# Tracksoar-Thermistor-Buzzer-Shield.net
KiCad netlist of a schematic drawn in EAGLE
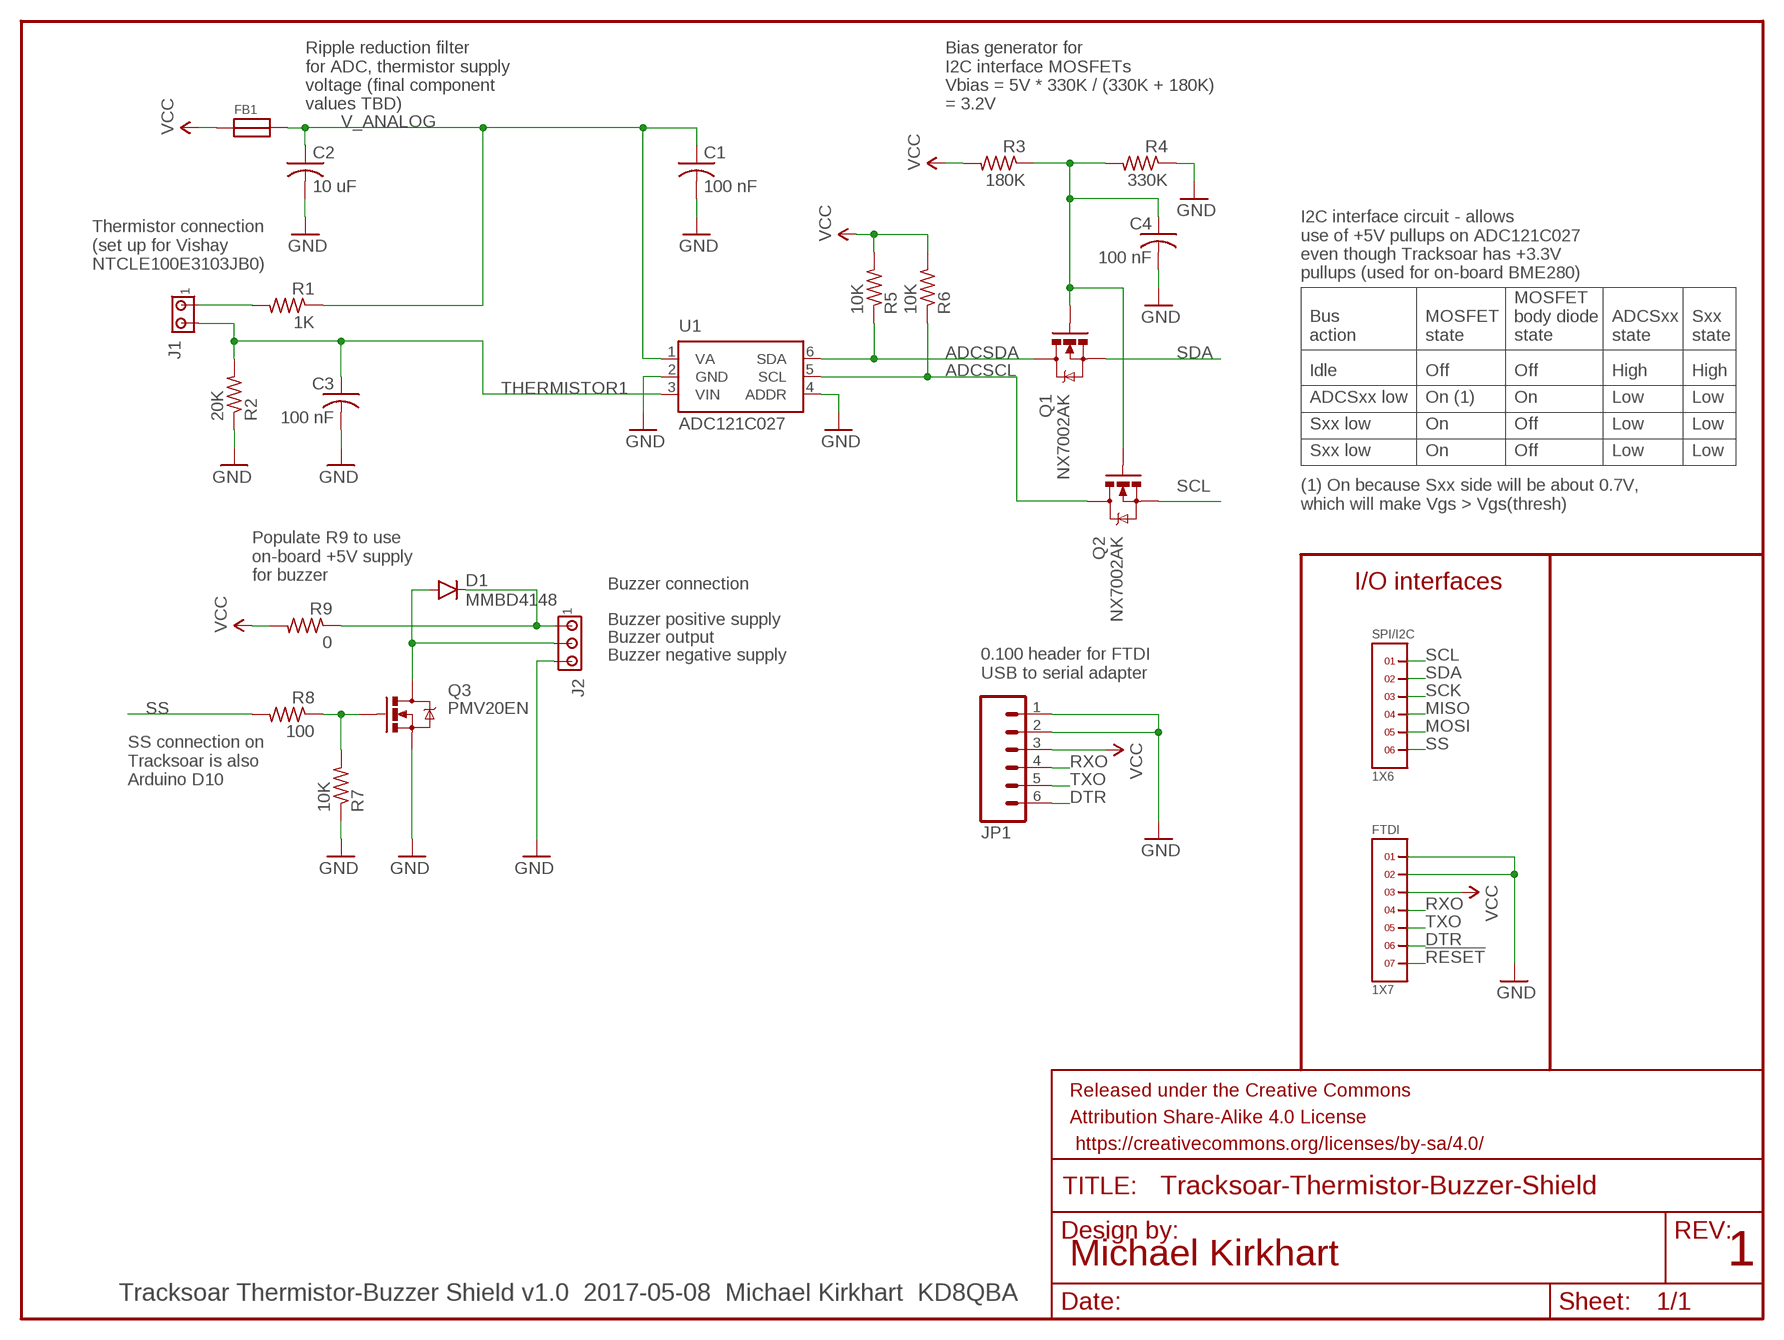
[diagram p0: schematic, sheet 1]

(export (version "E")
  (design (tool "Eeschema 10.0.6"))
  (components
    (comp (ref "C1")
      (value "100 nF")
      (footprint "eagle-import:C0805")
      (libsource (lib "eagle-import") (part "C-USC0805"))
    )
    (comp (ref "C2")
      (value "10 uF")
      (footprint "eagle-import:C0805")
      (libsource (lib "eagle-import") (part "C-USC0805"))
    )
    (comp (ref "C3")
      (value "100 nF")
      (footprint "eagle-import:C0805")
      (libsource (lib "eagle-import") (part "C-USC0805"))
    )
    (comp (ref "C4")
      (value "100 nF")
      (footprint "eagle-import:C0805")
      (libsource (lib "eagle-import") (part "C-USC0805"))
    )
    (comp (ref "D1")
      (value "MMBD4148")
      (footprint "eagle-import:SOT23-3")
      (libsource (lib "eagle-import") (part "DIODESOT23"))
    )
    (comp (ref "FB1")
      (value "FERRITE0805")
      (footprint "eagle-import:0805")
      (libsource (lib "eagle-import") (part "FERRITE0805"))
    )
    (comp (ref "FRAME1")
      (value "FRAME-LETTER")
      (footprint "eagle-import:CREATIVE_COMMONS")
      (libsource (lib "eagle-import") (part "FRAME-LETTER"))
    )
    (comp (ref "FTDI")
      (value "1X7")
      (footprint "eagle-import:1X7")
      (libsource (lib "eagle-import") (part "1X7"))
    )
    (comp (ref "J1")
      (value "MTA02-100")
      (footprint "eagle-import:10X02MTA")
      (libsource (lib "eagle-import") (part "MTA02-100"))
    )
    (comp (ref "J2")
      (value "MTA03-100")
      (footprint "eagle-import:10X03MTA")
      (libsource (lib "eagle-import") (part "MTA03-100"))
    )
    (comp (ref "JP1")
      (value "M06SILK_FEMALE_PTH")
      (footprint "eagle-import:1X06")
      (libsource (lib "eagle-import") (part "M06SILK_FEMALE_PTH"))
    )
    (comp (ref "Q1")
      (value "NX7002AK")
      (footprint "eagle-import:SOT23-3")
      (libsource (lib "eagle-import") (part "MOSFET-NCHANNELBSS123LT1G"))
    )
    (comp (ref "Q2")
      (value "NX7002AK")
      (footprint "eagle-import:SOT23-3")
      (libsource (lib "eagle-import") (part "MOSFET-NCHANNELBSS123LT1G"))
    )
    (comp (ref "Q3")
      (value "PMV20EN")
      (footprint "eagle-import:SOT23-3")
      (libsource (lib "eagle-import") (part "MOSFET-NCHANNELBSS123LT1G"))
    )
    (comp (ref "R1")
      (value "1K")
      (footprint "eagle-import:R0805")
      (libsource (lib "eagle-import") (part "R-US_R0805"))
    )
    (comp (ref "R2")
      (value "20K")
      (footprint "eagle-import:R0805")
      (libsource (lib "eagle-import") (part "R-US_R0805"))
    )
    (comp (ref "R3")
      (value "180K")
      (footprint "eagle-import:R0805")
      (libsource (lib "eagle-import") (part "R-US_R0805"))
    )
    (comp (ref "R4")
      (value "330K")
      (footprint "eagle-import:R0805")
      (libsource (lib "eagle-import") (part "R-US_R0805"))
    )
    (comp (ref "R5")
      (value "10K")
      (footprint "eagle-import:R0805")
      (libsource (lib "eagle-import") (part "R-US_R0805"))
    )
    (comp (ref "R6")
      (value "10K")
      (footprint "eagle-import:R0805")
      (libsource (lib "eagle-import") (part "R-US_R0805"))
    )
    (comp (ref "R7")
      (value "10K")
      (footprint "eagle-import:R0805")
      (libsource (lib "eagle-import") (part "R-US_R0805"))
    )
    (comp (ref "R8")
      (value "100")
      (footprint "eagle-import:R0805")
      (libsource (lib "eagle-import") (part "R-US_R0805"))
    )
    (comp (ref "R9")
      (value "0")
      (footprint "eagle-import:R0805")
      (libsource (lib "eagle-import") (part "R-US_R0805"))
    )
    (comp (ref "SPI/I2C")
      (value "1X6")
      (footprint "eagle-import:1X6")
      (libsource (lib "eagle-import") (part "1X6"))
    )
    (comp (ref "U1")
      (value "ADC121C027")
      (footprint "eagle-import:SOT23-6")
      (libsource (lib "eagle-import") (part "ADC121C027"))
    )
  )
  (nets
    (net (code "1") (name "/ADCSCL") (class "Default")
      (node (ref "Q2") (pin "3") (pinfunction "D_3") (pintype "passive"))
      (node (ref "R6") (pin "1") (pinfunction "1_1") (pintype "passive"))
      (node (ref "U1") (pin "5") (pinfunction "SCL_5") (pintype "input"))
    )
    (net (code "2") (name "/ADCSDA") (class "Default")
      (node (ref "Q1") (pin "3") (pinfunction "D_3") (pintype "passive"))
      (node (ref "R5") (pin "1") (pinfunction "1_1") (pintype "passive"))
      (node (ref "U1") (pin "6") (pinfunction "SDA_6") (pintype "input"))
    )
    (net (code "3") (name "/DTR") (class "Default")
      (node (ref "FTDI") (pin "6") (pinfunction "6_6") (pintype "bidirectional"))
      (node (ref "JP1") (pin "6") (pinfunction "6_6") (pintype "passive"))
    )
    (net (code "4") (name "/MISO") (class "Default")
      (node (ref "SPI/I2C") (pin "4") (pinfunction "4_4") (pintype "bidirectional"))
    )
    (net (code "5") (name "/MOSI") (class "Default")
      (node (ref "SPI/I2C") (pin "5") (pinfunction "5_5") (pintype "bidirectional"))
    )
    (net (code "6") (name "/RXO") (class "Default")
      (node (ref "FTDI") (pin "4") (pinfunction "4_4") (pintype "bidirectional"))
      (node (ref "JP1") (pin "4") (pinfunction "4_4") (pintype "passive"))
    )
    (net (code "7") (name "/SCK") (class "Default")
      (node (ref "SPI/I2C") (pin "3") (pinfunction "3_3") (pintype "bidirectional"))
    )
    (net (code "8") (name "/SCL") (class "Default")
      (node (ref "Q2") (pin "2") (pinfunction "S_2") (pintype "passive"))
      (node (ref "SPI/I2C") (pin "1") (pinfunction "1_1") (pintype "bidirectional"))
    )
    (net (code "9") (name "/SDA") (class "Default")
      (node (ref "Q1") (pin "2") (pinfunction "S_2") (pintype "passive"))
      (node (ref "SPI/I2C") (pin "2") (pinfunction "2_2") (pintype "bidirectional"))
    )
    (net (code "10") (name "/SS") (class "Default")
      (node (ref "R8") (pin "2") (pinfunction "2_2") (pintype "passive"))
      (node (ref "SPI/I2C") (pin "6") (pinfunction "6_6") (pintype "bidirectional"))
    )
    (net (code "11") (name "/THERMISTOR1") (class "Default")
      (node (ref "C3") (pin "1") (pinfunction "1_1") (pintype "passive"))
      (node (ref "J1") (pin "2") (pinfunction "2_2") (pintype "passive"))
      (node (ref "R2") (pin "2") (pinfunction "2_2") (pintype "passive"))
      (node (ref "U1") (pin "3") (pinfunction "VIN_3") (pintype "input"))
    )
    (net (code "12") (name "/TXO") (class "Default")
      (node (ref "FTDI") (pin "5") (pinfunction "5_5") (pintype "bidirectional"))
      (node (ref "JP1") (pin "5") (pinfunction "5_5") (pintype "passive"))
    )
    (net (code "13") (name "/V_ANALOG") (class "Default")
      (node (ref "C1") (pin "1") (pinfunction "1_1") (pintype "passive"))
      (node (ref "C2") (pin "1") (pinfunction "1_1") (pintype "passive"))
      (node (ref "FB1") (pin "2") (pinfunction "P$2_2") (pintype "bidirectional"))
      (node (ref "R1") (pin "1") (pinfunction "1_1") (pintype "passive"))
      (node (ref "U1") (pin "1") (pinfunction "VA_1") (pintype "input"))
    )
    (net (code "14") (name "/~{RESET}") (class "Default")
      (node (ref "FTDI") (pin "7") (pinfunction "7_7") (pintype "bidirectional"))
    )
    (net (code "15") (name "GND") (class "Default")
      (node (ref "C1") (pin "2") (pinfunction "2_2") (pintype "passive"))
      (node (ref "C2") (pin "2") (pinfunction "2_2") (pintype "passive"))
      (node (ref "C3") (pin "2") (pinfunction "2_2") (pintype "passive"))
      (node (ref "C4") (pin "2") (pinfunction "2_2") (pintype "passive"))
      (node (ref "FTDI") (pin "1") (pinfunction "1_1") (pintype "bidirectional"))
      (node (ref "FTDI") (pin "2") (pinfunction "2_2") (pintype "bidirectional"))
      (node (ref "J2") (pin "3") (pinfunction "3_3") (pintype "passive"))
      (node (ref "JP1") (pin "1") (pinfunction "1_1") (pintype "passive"))
      (node (ref "JP1") (pin "2") (pinfunction "2_2") (pintype "passive"))
      (node (ref "Q3") (pin "2") (pinfunction "S_2") (pintype "passive"))
      (node (ref "R2") (pin "1") (pinfunction "1_1") (pintype "passive"))
      (node (ref "R4") (pin "1") (pinfunction "1_1") (pintype "passive"))
      (node (ref "R7") (pin "1") (pinfunction "1_1") (pintype "passive"))
      (node (ref "U1") (pin "2") (pinfunction "GND_2") (pintype "input"))
      (node (ref "U1") (pin "4") (pinfunction "ADDR_4") (pintype "input"))
    )
    (net (code "16") (name "Net-(D1-A)") (class "Default")
      (node (ref "D1") (pin "1") (pinfunction "A_1") (pintype "passive"))
      (node (ref "J2") (pin "2") (pinfunction "2_2") (pintype "passive"))
      (node (ref "Q3") (pin "3") (pinfunction "D_3") (pintype "passive"))
    )
    (net (code "17") (name "Net-(D1-C)") (class "Default")
      (node (ref "D1") (pin "3") (pinfunction "C_3") (pintype "passive"))
      (node (ref "J2") (pin "1") (pinfunction "1_1") (pintype "passive"))
      (node (ref "R9") (pin "1") (pinfunction "1_1") (pintype "passive"))
    )
    (net (code "18") (name "Net-(J1-Pad1)") (class "Default")
      (node (ref "J1") (pin "1") (pinfunction "1_1") (pintype "passive"))
      (node (ref "R1") (pin "2") (pinfunction "2_2") (pintype "passive"))
    )
    (net (code "19") (name "Net-(Q1-G)") (class "Default")
      (node (ref "C4") (pin "1") (pinfunction "1_1") (pintype "passive"))
      (node (ref "Q1") (pin "1") (pinfunction "G_1") (pintype "passive"))
      (node (ref "Q2") (pin "1") (pinfunction "G_1") (pintype "passive"))
      (node (ref "R3") (pin "1") (pinfunction "1_1") (pintype "passive"))
      (node (ref "R4") (pin "2") (pinfunction "2_2") (pintype "passive"))
    )
    (net (code "20") (name "Net-(Q3-G)") (class "Default")
      (node (ref "Q3") (pin "1") (pinfunction "G_1") (pintype "passive"))
      (node (ref "R7") (pin "2") (pinfunction "2_2") (pintype "passive"))
      (node (ref "R8") (pin "1") (pinfunction "1_1") (pintype "passive"))
    )
    (net (code "21") (name "VCC") (class "Default")
      (node (ref "FB1") (pin "1") (pinfunction "P$1_1") (pintype "bidirectional"))
      (node (ref "FTDI") (pin "3") (pinfunction "3_3") (pintype "bidirectional"))
      (node (ref "JP1") (pin "3") (pinfunction "3_3") (pintype "passive"))
      (node (ref "R3") (pin "2") (pinfunction "2_2") (pintype "passive"))
      (node (ref "R5") (pin "2") (pinfunction "2_2") (pintype "passive"))
      (node (ref "R6") (pin "2") (pinfunction "2_2") (pintype "passive"))
      (node (ref "R9") (pin "2") (pinfunction "2_2") (pintype "passive"))
    )
  )
)
